# GainCHL.net
KiCad netlist of a schematic drawn in Altium Designer
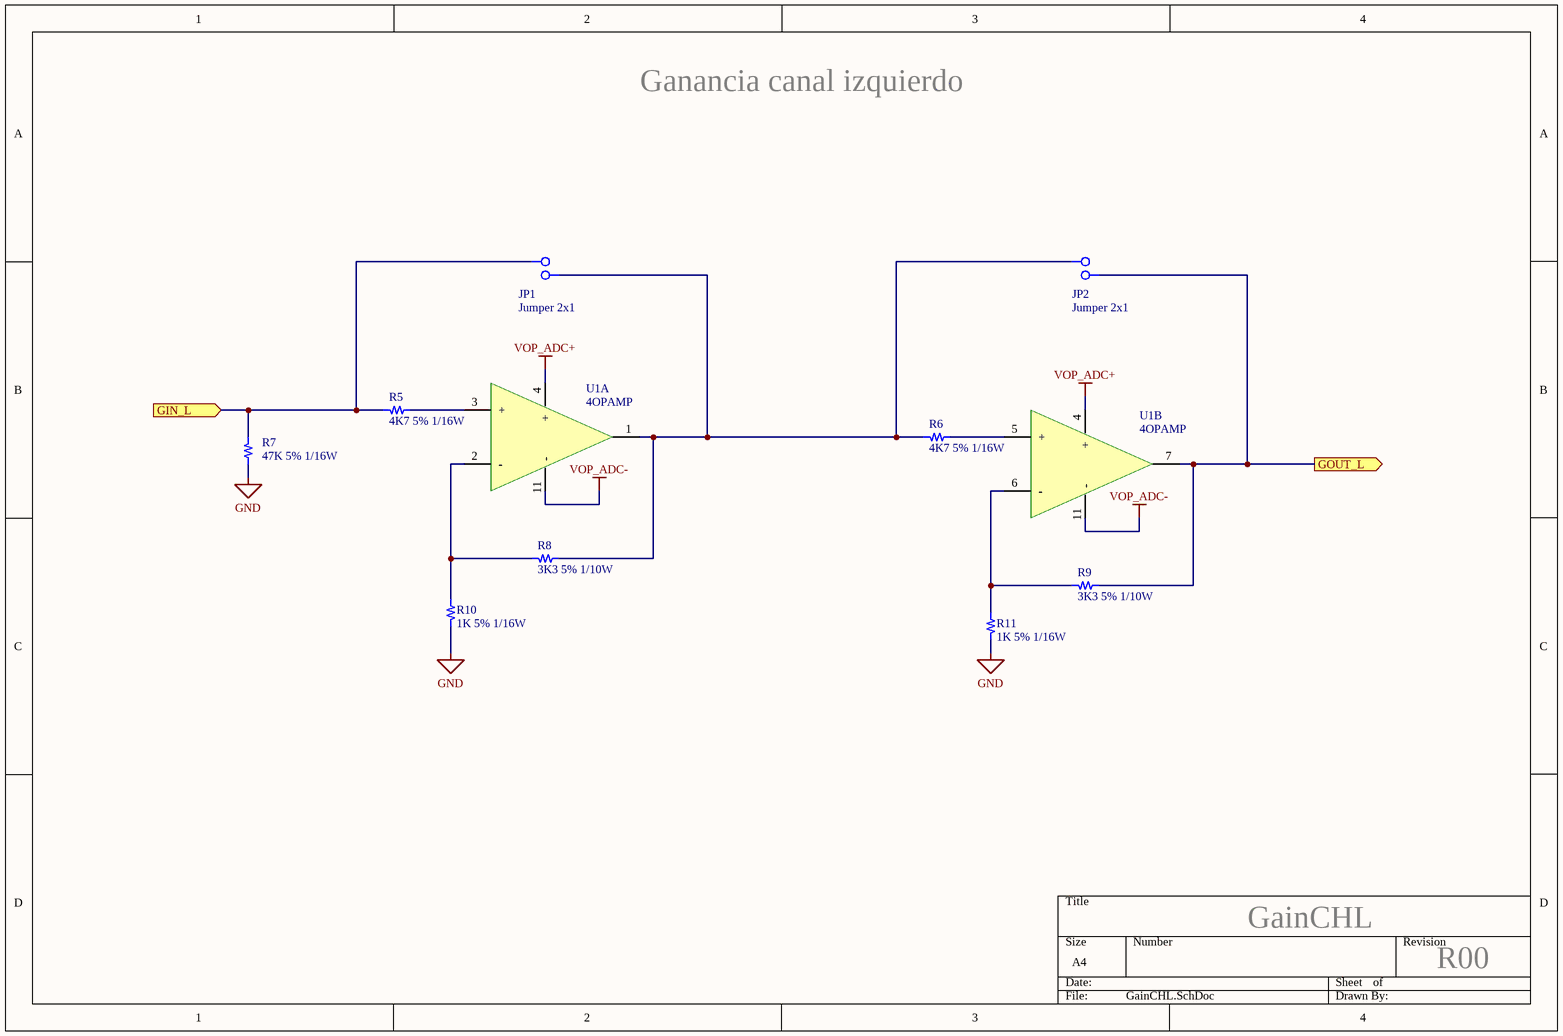
[diagram p0: GainCHL.SchDoc]

(export (version "E")
  (design (tool "Eeschema 10.0.6"))
  (components
    (comp (ref "JP1")
      (value "Jumper 2x1")
      (footprint "Conn_2_1")
      (libsource (lib "Radios_Comunitarias") (part "Jumper 2x1"))
    )
    (comp (ref "JP2")
      (value "Jumper 2x1")
      (footprint "Conn_2_1")
      (libsource (lib "Radios_Comunitarias") (part "Jumper 2x1"))
    )
    (comp (ref "R5")
      (value "4K7 5% 1/16W")
      (footprint "R_0805")
      (description "Resistencia")
      (libsource (lib "Radios_Comunitarias") (part "Resistor"))
    )
    (comp (ref "R6")
      (value "4K7 5% 1/16W")
      (footprint "R_0805")
      (description "Resistencia")
      (libsource (lib "Radios_Comunitarias") (part "Resistor"))
    )
    (comp (ref "R7")
      (value "47K 5% 1/16W")
      (footprint "R_0805")
      (description "Resistencia")
      (libsource (lib "Radios_Comunitarias") (part "Resistor"))
    )
    (comp (ref "R8")
      (value "3K3 5% 1/10W")
      (footprint "R_0805")
      (description "Resistencia")
      (libsource (lib "Radios_Comunitarias") (part "Resistor"))
    )
    (comp (ref "R9")
      (value "3K3 5% 1/10W")
      (footprint "R_0805")
      (description "Resistencia")
      (libsource (lib "Radios_Comunitarias") (part "Resistor"))
    )
    (comp (ref "R10")
      (value "1K 5% 1/16W")
      (footprint "R_0805")
      (description "Resistencia")
      (libsource (lib "Radios_Comunitarias") (part "Resistor"))
    )
    (comp (ref "R11")
      (value "1K 5% 1/16W")
      (footprint "R_0805")
      (description "Resistencia")
      (libsource (lib "Radios_Comunitarias") (part "Resistor"))
    )
    (comp (ref "U1")
      (value "4OPAMP")
      (footprint "SOIC14")
      (description "Integrado con 4 operacionales")
      (libsource (lib "Radios_Comunitarias") (part "4OPAMP"))
    )
  )
  (nets
    (net (code "1") (name "/GIN_L") (class "Default")
      (node (ref "JP1") (pin "1") (pinfunction "1_1") (pintype "passive"))
      (node (ref "R5") (pin "2") (pinfunction "2_2") (pintype "passive"))
      (node (ref "R7") (pin "2") (pinfunction "2_2") (pintype "passive"))
    )
    (net (code "2") (name "/GOUT_L") (class "Default")
      (node (ref "JP2") (pin "2") (pinfunction "2_2") (pintype "passive"))
      (node (ref "R9") (pin "1") (pinfunction "1_1") (pintype "passive"))
      (node (ref "U1") (pin "7") (pinfunction "OUT_7") (pintype "passive"))
    )
    (net (code "3") (name "GND") (class "Default")
      (node (ref "R10") (pin "2") (pinfunction "2_2") (pintype "passive"))
      (node (ref "R11") (pin "2") (pinfunction "2_2") (pintype "passive"))
      (node (ref "R7") (pin "1") (pinfunction "1_1") (pintype "passive"))
    )
    (net (code "4") (name "Net-(R5-Pad1)") (class "Default")
      (node (ref "R5") (pin "1") (pinfunction "1_1") (pintype "passive"))
      (node (ref "U1") (pin "3") (pinfunction "+_3") (pintype "passive"))
    )
    (net (code "5") (name "Net-(R6-Pad1)") (class "Default")
      (node (ref "R6") (pin "1") (pinfunction "1_1") (pintype "passive"))
      (node (ref "U1") (pin "5") (pinfunction "+_5") (pintype "passive"))
    )
    (net (code "6") (name "Net-(R10-Pad1)") (class "Default")
      (node (ref "R10") (pin "1") (pinfunction "1_1") (pintype "passive"))
      (node (ref "R8") (pin "2") (pinfunction "2_2") (pintype "passive"))
      (node (ref "U1") (pin "2") (pinfunction "-_2") (pintype "passive"))
    )
    (net (code "7") (name "Net-(R11-Pad1)") (class "Default")
      (node (ref "R11") (pin "1") (pinfunction "1_1") (pintype "passive"))
      (node (ref "R9") (pin "2") (pinfunction "2_2") (pintype "passive"))
      (node (ref "U1") (pin "6") (pinfunction "-_6") (pintype "passive"))
    )
    (net (code "8") (name "Net-(U1A-OUT)") (class "Default")
      (node (ref "JP1") (pin "2") (pinfunction "2_2") (pintype "passive"))
      (node (ref "JP2") (pin "1") (pinfunction "1_1") (pintype "passive"))
      (node (ref "R6") (pin "2") (pinfunction "2_2") (pintype "passive"))
      (node (ref "R8") (pin "1") (pinfunction "1_1") (pintype "passive"))
      (node (ref "U1") (pin "1") (pinfunction "OUT_1") (pintype "passive"))
    )
    (net (code "9") (name "VOP_ADC+") (class "Default")
      (node (ref "U1") (pin "4") (pinfunction "+_4") (pintype "power_in"))
    )
    (net (code "10") (name "VOP_ADC-") (class "Default")
      (node (ref "U1") (pin "11") (pinfunction "-_11") (pintype "passive"))
    )
  )
)
